# Cigarette-Smoke-Detection-and-Odor-Neutr.net
KiCad netlist of a schematic drawn in Altium Designer
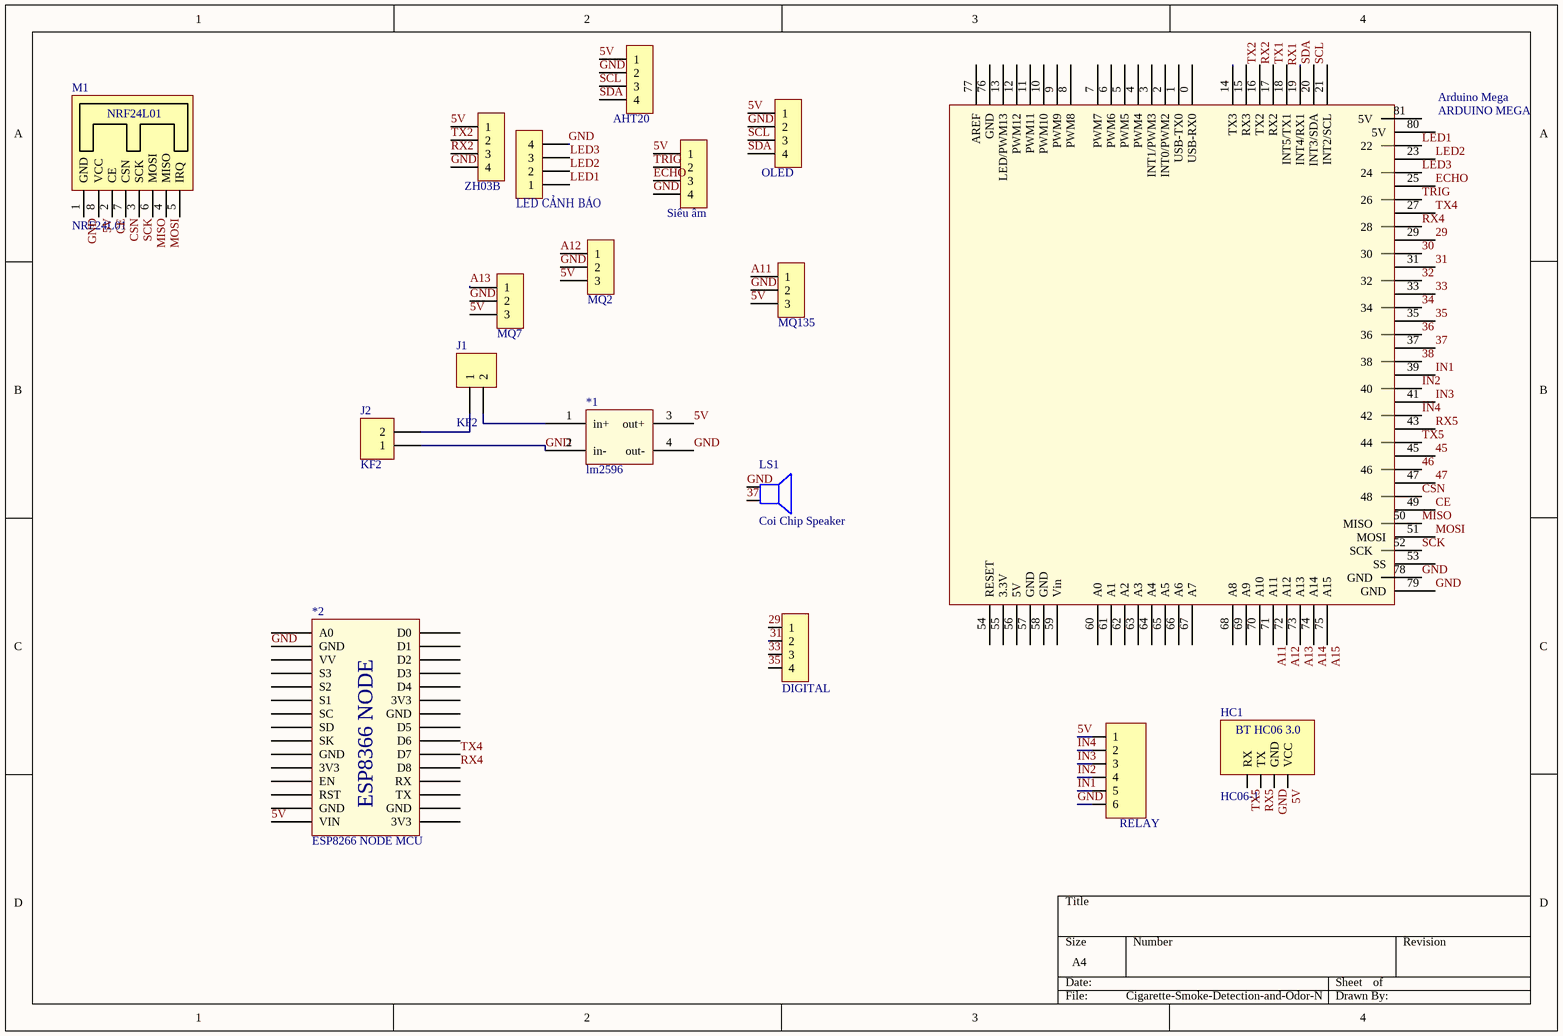
[diagram p0: Cigarette-Smoke-Detection-and-Odor-Neutralization-Robot.SchDoc]

(export (version "E")
  (design (tool "Eeschema 10.0.6"))
  (components
    (comp (ref "*1")
      (value "lm2596")
      (footprint "LM2596:PCBComponent_1")
      (libsource (lib "LM2596") (part "lm2596"))
    )
    (comp (ref "*2")
      (value "ESP8266 NODE MCU")
      (footprint "ESP8266 NODE MCU")
      (libsource (lib "Module1") (part "ESP8266 NODE MCU"))
    )
    (comp (ref "Arduino Mega")
      (value "ARDUINO MEGA")
      (footprint "ARDUINO MEGA")
      (libsource (lib "Arduino") (part "ARDUINO MEGA"))
    )
    (comp (ref "H1")
      (value "AHT20")
      (footprint "XH2.54M-4")
      (description "Cắm")
      (libsource (lib "Header") (part "Header 4P 2.54 Duc Thang"))
    )
    (comp (ref "H2")
      (value "OLED")
      (footprint "XH2.54M-4")
      (description "Cắm")
      (libsource (lib "Header") (part "Header 4P 2.54 Duc Thang"))
    )
    (comp (ref "H3")
      (value "ZH03B")
      (footprint "XH2.54M-4")
      (description "Cắm")
      (libsource (lib "Header") (part "Header 4P 2.54 Duc Thang"))
    )
    (comp (ref "H4")
      (value "LED CẢNH BÁO")
      (footprint "XH2.54M-4")
      (description "Cắm")
      (libsource (lib "") (part "Header 4P 2.54 Duc Thang_1"))
    )
    (comp (ref "H5")
      (value "Siêu âm")
      (footprint "XH2.54M-4")
      (description "Cắm")
      (libsource (lib "Header") (part "Header 4P 2.54 Duc Thang"))
    )
    (comp (ref "H6")
      (value "MQ2")
      (footprint "XH2.54M-3")
      (description "Cắm")
      (libsource (lib "Header") (part "Header 3P 2.54 Duc Thang"))
    )
    (comp (ref "H7")
      (value "MQ135")
      (footprint "XH2.54M-3")
      (description "Cắm")
      (libsource (lib "Header") (part "Header 3P 2.54 Duc Thang"))
    )
    (comp (ref "H8")
      (value "MQ7")
      (footprint "XH2.54M-3")
      (description "Cắm")
      (libsource (lib "Header") (part "Header 3P 2.54 Duc Thang"))
    )
    (comp (ref "H9")
      (value "RELAY")
      (footprint "JP 1x6 DT")
      (description "Cắm")
      (libsource (lib "Jump") (part "JP 1x6 2.54 Duc Thang"))
    )
    (comp (ref "HC1")
      (value "HC06-1")
      (footprint "HC06-1")
      (fields
        (field (name "MANUFACTURER") "Würth Elektronik eiSos GmbH")
        (field (name "PARTNO") "613004143121")
        (field (name "CREATED BY") "Karrer Zheng")
      )
      (libsource (lib "LIBRARY1") (part "HC06-1"))
    )
    (comp (ref "J1")
      (value "KF2")
      (footprint "KF2-3.5")
      (fields
        (field (name "MANUFACTURER") "Würth Elektronik eiSos GmbH")
        (field (name "PARTNO") "691103110002")
        (field (name "CREATED BY") "Karrer Zheng")
      )
      (libsource (lib "LIBRARY1") (part "KF2"))
    )
    (comp (ref "J2")
      (value "KF2")
      (footprint "KF2-3.5")
      (fields
        (field (name "MANUFACTURER") "Würth Elektronik eiSos GmbH")
        (field (name "PARTNO") "691103110002")
        (field (name "CREATED BY") "Karrer Zheng")
      )
      (libsource (lib "") (part "KF2_1"))
    )
    (comp (ref "JP1")
      (value "DIGITAL")
      (footprint "JP 1x4 DT")
      (description "Cắm")
      (libsource (lib "Jump") (part "JP 1x4 2.54 Duc Thang"))
    )
    (comp (ref "LS1")
      (value "Coi Chip Speaker")
      (footprint "Coi Chip Speacker")
      (description "Còi chip")
      (libsource (lib "Altium_Lib_by_KhueNguyenCreator") (part "Coi Chip Speaker"))
    )
    (comp (ref "M1") (value "NRF24L01") (footprint "NRF24L01") (libsource (lib "LIBRARY1") (part "NRF24L01")))
  )
  (nets
    (net (code "1") (name "/5V") (class "Default")
      (node (ref "*1") (pin "3") (pinfunction "out+_3") (pintype "passive"))
      (node (ref "*2") (pin "15") (pinfunction "VIN_15") (pintype "passive"))
      (node (ref "H1") (pin "1") (pinfunction "1_1") (pintype "passive"))
      (node (ref "H2") (pin "1") (pinfunction "1_1") (pintype "passive"))
      (node (ref "H3") (pin "1") (pinfunction "1_1") (pintype "passive"))
      (node (ref "H5") (pin "1") (pinfunction "1_1") (pintype "passive"))
      (node (ref "H6") (pin "3") (pinfunction "3_3") (pintype "passive"))
      (node (ref "H7") (pin "3") (pinfunction "3_3") (pintype "passive"))
      (node (ref "H8") (pin "3") (pinfunction "3_3") (pintype "passive"))
      (node (ref "H9") (pin "1") (pinfunction "1_1") (pintype "passive"))
      (node (ref "HC1") (pin "4") (pinfunction "VCC_4") (pintype "passive"))
      (node (ref "M1") (pin "8") (pinfunction "VCC_8") (pintype "passive"))
    )
    (net (code "2") (name "/29") (class "Default")
      (node (ref "Arduino Mega") (pin "29") (pinfunction "29_29") (pintype "passive"))
      (node (ref "JP1") (pin "1") (pinfunction "1_1") (pintype "passive"))
    )
    (net (code "3") (name "/30") (class "Default")
      (node (ref "Arduino Mega") (pin "30") (pinfunction "30_30") (pintype "passive"))
    )
    (net (code "4") (name "/31") (class "Default")
      (node (ref "Arduino Mega") (pin "31") (pinfunction "31_31") (pintype "passive"))
      (node (ref "JP1") (pin "2") (pinfunction "2_2") (pintype "passive"))
    )
    (net (code "5") (name "/32") (class "Default")
      (node (ref "Arduino Mega") (pin "32") (pinfunction "32_32") (pintype "passive"))
    )
    (net (code "6") (name "/33") (class "Default")
      (node (ref "Arduino Mega") (pin "33") (pinfunction "33_33") (pintype "passive"))
      (node (ref "JP1") (pin "3") (pinfunction "3_3") (pintype "passive"))
    )
    (net (code "7") (name "/34") (class "Default")
      (node (ref "Arduino Mega") (pin "34") (pinfunction "34_34") (pintype "passive"))
    )
    (net (code "8") (name "/35") (class "Default")
      (node (ref "Arduino Mega") (pin "35") (pinfunction "35_35") (pintype "passive"))
      (node (ref "JP1") (pin "4") (pinfunction "4_4") (pintype "passive"))
    )
    (net (code "9") (name "/36") (class "Default")
      (node (ref "Arduino Mega") (pin "36") (pinfunction "36_36") (pintype "passive"))
    )
    (net (code "10") (name "/37") (class "Default")
      (node (ref "Arduino Mega") (pin "37") (pinfunction "37_37") (pintype "passive"))
      (node (ref "LS1") (pin "2") (pinfunction "2_2") (pintype "passive"))
    )
    (net (code "11") (name "/38") (class "Default")
      (node (ref "Arduino Mega") (pin "38") (pinfunction "38_38") (pintype "passive"))
    )
    (net (code "12") (name "/45") (class "Default")
      (node (ref "Arduino Mega") (pin "45") (pinfunction "45_45") (pintype "passive"))
    )
    (net (code "13") (name "/46") (class "Default")
      (node (ref "Arduino Mega") (pin "46") (pinfunction "46_46") (pintype "passive"))
    )
    (net (code "14") (name "/47") (class "Default")
      (node (ref "Arduino Mega") (pin "47") (pinfunction "47_47") (pintype "passive"))
    )
    (net (code "15") (name "/A11") (class "Default")
      (node (ref "Arduino Mega") (pin "71") (pinfunction "A11_71") (pintype "passive"))
      (node (ref "H7") (pin "1") (pinfunction "1_1") (pintype "passive"))
    )
    (net (code "16") (name "/A12") (class "Default")
      (node (ref "Arduino Mega") (pin "72") (pinfunction "A12_72") (pintype "passive"))
      (node (ref "H6") (pin "1") (pinfunction "1_1") (pintype "passive"))
    )
    (net (code "17") (name "/A13") (class "Default")
      (node (ref "Arduino Mega") (pin "73") (pinfunction "A13_73") (pintype "passive"))
      (node (ref "H8") (pin "1") (pinfunction "1_1") (pintype "passive"))
    )
    (net (code "18") (name "/A14") (class "Default")
      (node (ref "Arduino Mega") (pin "74") (pinfunction "A14_74") (pintype "passive"))
    )
    (net (code "19") (name "/A15") (class "Default")
      (node (ref "Arduino Mega") (pin "75") (pinfunction "A15_75") (pintype "passive"))
    )
    (net (code "20") (name "/CE") (class "Default")
      (node (ref "Arduino Mega") (pin "49") (pinfunction "49_49") (pintype "passive"))
      (node (ref "M1") (pin "2") (pinfunction "CE_2") (pintype "passive"))
    )
    (net (code "21") (name "/CSN") (class "Default")
      (node (ref "Arduino Mega") (pin "48") (pinfunction "48_48") (pintype "passive"))
      (node (ref "M1") (pin "7") (pinfunction "CSN_7") (pintype "passive"))
    )
    (net (code "22") (name "/ECHO") (class "Default")
      (node (ref "Arduino Mega") (pin "25") (pinfunction "25_25") (pintype "passive"))
      (node (ref "H5") (pin "3") (pinfunction "3_3") (pintype "passive"))
    )
    (net (code "23") (name "/GND") (class "Default")
      (node (ref "*1") (pin "2") (pinfunction "in-_2") (pintype "passive"))
      (node (ref "*1") (pin "4") (pinfunction "out-_4") (pintype "passive"))
      (node (ref "*2") (pin "2") (pinfunction "GND_2") (pintype "passive"))
      (node (ref "Arduino Mega") (pin "78") (pinfunction "GND_78") (pintype "passive"))
      (node (ref "Arduino Mega") (pin "79") (pinfunction "GND_79") (pintype "passive"))
      (node (ref "H1") (pin "2") (pinfunction "2_2") (pintype "passive"))
      (node (ref "H2") (pin "2") (pinfunction "2_2") (pintype "passive"))
      (node (ref "H3") (pin "4") (pinfunction "4_4") (pintype "passive"))
      (node (ref "H4") (pin "4") (pinfunction "4_4") (pintype "passive"))
      (node (ref "H5") (pin "4") (pinfunction "4_4") (pintype "passive"))
      (node (ref "H6") (pin "2") (pinfunction "2_2") (pintype "passive"))
      (node (ref "H7") (pin "2") (pinfunction "2_2") (pintype "passive"))
      (node (ref "H8") (pin "2") (pinfunction "2_2") (pintype "passive"))
      (node (ref "H9") (pin "6") (pinfunction "6_6") (pintype "passive"))
      (node (ref "HC1") (pin "3") (pinfunction "GND_3") (pintype "passive"))
      (node (ref "J2") (pin "1") (pinfunction "1_1") (pintype "passive"))
      (node (ref "LS1") (pin "1") (pinfunction "1_1") (pintype "passive"))
      (node (ref "M1") (pin "1") (pinfunction "GND_1") (pintype "passive"))
    )
    (net (code "24") (name "/IN1") (class "Default")
      (node (ref "Arduino Mega") (pin "39") (pinfunction "39_39") (pintype "passive"))
      (node (ref "H9") (pin "5") (pinfunction "5_5") (pintype "passive"))
    )
    (net (code "25") (name "/IN2") (class "Default")
      (node (ref "Arduino Mega") (pin "40") (pinfunction "40_40") (pintype "passive"))
      (node (ref "H9") (pin "4") (pinfunction "4_4") (pintype "passive"))
    )
    (net (code "26") (name "/IN3") (class "Default")
      (node (ref "Arduino Mega") (pin "41") (pinfunction "41_41") (pintype "passive"))
      (node (ref "H9") (pin "3") (pinfunction "3_3") (pintype "passive"))
    )
    (net (code "27") (name "/IN4") (class "Default")
      (node (ref "Arduino Mega") (pin "42") (pinfunction "42_42") (pintype "passive"))
      (node (ref "H9") (pin "2") (pinfunction "2_2") (pintype "passive"))
    )
    (net (code "28") (name "/LED1") (class "Default")
      (node (ref "Arduino Mega") (pin "22") (pinfunction "22_22") (pintype "passive"))
      (node (ref "H4") (pin "1") (pinfunction "1_1") (pintype "passive"))
    )
    (net (code "29") (name "/LED2") (class "Default")
      (node (ref "Arduino Mega") (pin "23") (pinfunction "23_23") (pintype "passive"))
      (node (ref "H4") (pin "2") (pinfunction "2_2") (pintype "passive"))
    )
    (net (code "30") (name "/LED3") (class "Default")
      (node (ref "Arduino Mega") (pin "24") (pinfunction "24_24") (pintype "passive"))
      (node (ref "H4") (pin "3") (pinfunction "3_3") (pintype "passive"))
    )
    (net (code "31") (name "/MISO") (class "Default")
      (node (ref "Arduino Mega") (pin "50") (pinfunction "MISO_50") (pintype "passive"))
      (node (ref "M1") (pin "6") (pinfunction "MOSI_6") (pintype "passive"))
    )
    (net (code "32") (name "/MOSI") (class "Default")
      (node (ref "Arduino Mega") (pin "51") (pinfunction "MOSI_51") (pintype "passive"))
      (node (ref "M1") (pin "4") (pinfunction "MISO_4") (pintype "passive"))
    )
    (net (code "33") (name "/RX1") (class "Default")
      (node (ref "Arduino Mega") (pin "19") (pinfunction "INT4/RX1_19") (pintype "passive"))
    )
    (net (code "34") (name "/RX2") (class "Default")
      (node (ref "Arduino Mega") (pin "17") (pinfunction "RX2_17") (pintype "passive"))
      (node (ref "H3") (pin "3") (pinfunction "3_3") (pintype "passive"))
    )
    (net (code "35") (name "/RX4") (class "Default")
      (node (ref "*2") (pin "20") (pinfunction "D8_20") (pintype "passive"))
      (node (ref "Arduino Mega") (pin "28") (pinfunction "28_28") (pintype "passive"))
    )
    (net (code "36") (name "/RX5") (class "Default")
      (node (ref "Arduino Mega") (pin "43") (pinfunction "43_43") (pintype "passive"))
      (node (ref "HC1") (pin "2") (pinfunction "TX_2") (pintype "passive"))
    )
    (net (code "37") (name "/SCK") (class "Default")
      (node (ref "Arduino Mega") (pin "52") (pinfunction "SCK_52") (pintype "passive"))
      (node (ref "M1") (pin "3") (pinfunction "SCK_3") (pintype "passive"))
    )
    (net (code "38") (name "/SCL") (class "Default")
      (node (ref "Arduino Mega") (pin "21") (pinfunction "INT2/SCL_21") (pintype "passive"))
      (node (ref "H1") (pin "3") (pinfunction "3_3") (pintype "passive"))
      (node (ref "H2") (pin "3") (pinfunction "3_3") (pintype "passive"))
    )
    (net (code "39") (name "/SDA") (class "Default")
      (node (ref "Arduino Mega") (pin "20") (pinfunction "INT3/SDA_20") (pintype "passive"))
      (node (ref "H1") (pin "4") (pinfunction "4_4") (pintype "passive"))
      (node (ref "H2") (pin "4") (pinfunction "4_4") (pintype "passive"))
    )
    (net (code "40") (name "/TRIG") (class "Default")
      (node (ref "Arduino Mega") (pin "26") (pinfunction "26_26") (pintype "passive"))
      (node (ref "H5") (pin "2") (pinfunction "2_2") (pintype "passive"))
    )
    (net (code "41") (name "/TX1") (class "Default")
      (node (ref "Arduino Mega") (pin "18") (pinfunction "INT5/TX1_18") (pintype "passive"))
    )
    (net (code "42") (name "/TX2") (class "Default")
      (node (ref "Arduino Mega") (pin "16") (pinfunction "TX2_16") (pintype "passive"))
      (node (ref "H3") (pin "2") (pinfunction "2_2") (pintype "passive"))
    )
    (net (code "43") (name "/TX4") (class "Default")
      (node (ref "*2") (pin "21") (pinfunction "D7_21") (pintype "passive"))
      (node (ref "Arduino Mega") (pin "27") (pinfunction "27_27") (pintype "passive"))
    )
    (net (code "44") (name "/TX5") (class "Default")
      (node (ref "Arduino Mega") (pin "44") (pinfunction "44_44") (pintype "passive"))
      (node (ref "HC1") (pin "1") (pinfunction "RX_1") (pintype "passive"))
    )
    (net (code "45") (name "Net-(*1-in+)") (class "Default")
      (node (ref "*1") (pin "1") (pinfunction "in+_1") (pintype "passive"))
      (node (ref "J1") (pin "2") (pinfunction "2_2") (pintype "passive"))
    )
    (net (code "46") (name "Net-(J1-Pad1)") (class "Default")
      (node (ref "J1") (pin "1") (pinfunction "1_1") (pintype "passive"))
      (node (ref "J2") (pin "2") (pinfunction "2_2") (pintype "passive"))
    )
    (net (code "47") (name "unconnected-(*2-3V3-Pad11)") (class "Default")
      (node (ref "*2") (pin "11") (pinfunction "3V3_11") (pintype "passive"))
    )
    (net (code "48") (name "unconnected-(*2-3V3-Pad16)") (class "Default")
      (node (ref "*2") (pin "16") (pinfunction "3V3_16") (pintype "passive"))
    )
    (net (code "49") (name "unconnected-(*2-3V3-Pad25)") (class "Default")
      (node (ref "*2") (pin "25") (pinfunction "3V3_25") (pintype "passive"))
    )
    (net (code "50") (name "unconnected-(*2-A0-Pad1)") (class "Default")
      (node (ref "*2") (pin "1") (pinfunction "A0_1") (pintype "passive"))
    )
    (net (code "51") (name "unconnected-(*2-D0-Pad30)") (class "Default")
      (node (ref "*2") (pin "30") (pinfunction "D0_30") (pintype "passive"))
    )
    (net (code "52") (name "unconnected-(*2-D1-Pad29)") (class "Default")
      (node (ref "*2") (pin "29") (pinfunction "D1_29") (pintype "passive"))
    )
    (net (code "53") (name "unconnected-(*2-D2-Pad28)") (class "Default")
      (node (ref "*2") (pin "28") (pinfunction "D2_28") (pintype "passive"))
    )
    (net (code "54") (name "unconnected-(*2-D3-Pad27)") (class "Default")
      (node (ref "*2") (pin "27") (pinfunction "D3_27") (pintype "passive"))
    )
    (net (code "55") (name "unconnected-(*2-D4-Pad26)") (class "Default")
      (node (ref "*2") (pin "26") (pinfunction "D4_26") (pintype "passive"))
    )
    (net (code "56") (name "unconnected-(*2-D5-Pad23)") (class "Default")
      (node (ref "*2") (pin "23") (pinfunction "D5_23") (pintype "passive"))
    )
    (net (code "57") (name "unconnected-(*2-D6-Pad22)") (class "Default")
      (node (ref "*2") (pin "22") (pinfunction "D6_22") (pintype "passive"))
    )
    (net (code "58") (name "unconnected-(*2-EN-Pad12)") (class "Default")
      (node (ref "*2") (pin "12") (pinfunction "EN_12") (pintype "passive"))
    )
    (net (code "59") (name "unconnected-(*2-GND-Pad10)") (class "Default")
      (node (ref "*2") (pin "10") (pinfunction "GND_10") (pintype "passive"))
    )
    (net (code "60") (name "unconnected-(*2-GND-Pad14)") (class "Default")
      (node (ref "*2") (pin "14") (pinfunction "GND_14") (pintype "passive"))
    )
    (net (code "61") (name "unconnected-(*2-GND-Pad17)") (class "Default")
      (node (ref "*2") (pin "17") (pinfunction "GND_17") (pintype "passive"))
    )
    (net (code "62") (name "unconnected-(*2-GND-Pad24)") (class "Default")
      (node (ref "*2") (pin "24") (pinfunction "GND_24") (pintype "passive"))
    )
    (net (code "63") (name "unconnected-(*2-RST-Pad13)") (class "Default")
      (node (ref "*2") (pin "13") (pinfunction "RST_13") (pintype "passive"))
    )
    (net (code "64") (name "unconnected-(*2-RX-Pad19)") (class "Default")
      (node (ref "*2") (pin "19") (pinfunction "RX_19") (pintype "passive"))
    )
    (net (code "65") (name "unconnected-(*2-S1-Pad6)") (class "Default")
      (node (ref "*2") (pin "6") (pinfunction "S1_6") (pintype "passive"))
    )
    (net (code "66") (name "unconnected-(*2-S2-Pad5)") (class "Default")
      (node (ref "*2") (pin "5") (pinfunction "S2_5") (pintype "passive"))
    )
    (net (code "67") (name "unconnected-(*2-S3-Pad4)") (class "Default")
      (node (ref "*2") (pin "4") (pinfunction "S3_4") (pintype "passive"))
    )
    (net (code "68") (name "unconnected-(*2-SC-Pad7)") (class "Default")
      (node (ref "*2") (pin "7") (pinfunction "SC_7") (pintype "passive"))
    )
    (net (code "69") (name "unconnected-(*2-SD-Pad8)") (class "Default")
      (node (ref "*2") (pin "8") (pinfunction "SD_8") (pintype "passive"))
    )
    (net (code "70") (name "unconnected-(*2-SK-Pad9)") (class "Default")
      (node (ref "*2") (pin "9") (pinfunction "SK_9") (pintype "passive"))
    )
    (net (code "71") (name "unconnected-(*2-TX-Pad18)") (class "Default")
      (node (ref "*2") (pin "18") (pinfunction "TX_18") (pintype "passive"))
    )
    (net (code "72") (name "unconnected-(*2-VV-Pad3)") (class "Default")
      (node (ref "*2") (pin "3") (pinfunction "VV_3") (pintype "passive"))
    )
    (net (code "73") (name "unconnected-(Arduino Mega-3.3V-Pad55)") (class "Default")
      (node (ref "Arduino Mega") (pin "55") (pinfunction "3.3V_55") (pintype "passive"))
    )
    (net (code "74") (name "unconnected-(Arduino Mega-5V-Pad56)") (class "Default")
      (node (ref "Arduino Mega") (pin "56") (pinfunction "5V_56") (pintype "passive"))
    )
    (net (code "75") (name "unconnected-(Arduino Mega-5V-Pad80)") (class "Default")
      (node (ref "Arduino Mega") (pin "80") (pinfunction "5V_80") (pintype "passive"))
    )
    (net (code "76") (name "unconnected-(Arduino Mega-5V-Pad81)") (class "Default")
      (node (ref "Arduino Mega") (pin "81") (pinfunction "5V_81") (pintype "passive"))
    )
    (net (code "77") (name "unconnected-(Arduino Mega-A0-Pad60)") (class "Default")
      (node (ref "Arduino Mega") (pin "60") (pinfunction "A0_60") (pintype "passive"))
    )
    (net (code "78") (name "unconnected-(Arduino Mega-A1-Pad61)") (class "Default")
      (node (ref "Arduino Mega") (pin "61") (pinfunction "A1_61") (pintype "passive"))
    )
    (net (code "79") (name "unconnected-(Arduino Mega-A2-Pad62)") (class "Default")
      (node (ref "Arduino Mega") (pin "62") (pinfunction "A2_62") (pintype "passive"))
    )
    (net (code "80") (name "unconnected-(Arduino Mega-A3-Pad63)") (class "Default")
      (node (ref "Arduino Mega") (pin "63") (pinfunction "A3_63") (pintype "passive"))
    )
    (net (code "81") (name "unconnected-(Arduino Mega-A4-Pad64)") (class "Default")
      (node (ref "Arduino Mega") (pin "64") (pinfunction "A4_64") (pintype "passive"))
    )
    (net (code "82") (name "unconnected-(Arduino Mega-A5-Pad65)") (class "Default")
      (node (ref "Arduino Mega") (pin "65") (pinfunction "A5_65") (pintype "passive"))
    )
    (net (code "83") (name "unconnected-(Arduino Mega-A6-Pad66)") (class "Default")
      (node (ref "Arduino Mega") (pin "66") (pinfunction "A6_66") (pintype "passive"))
    )
    (net (code "84") (name "unconnected-(Arduino Mega-A7-Pad67)") (class "Default")
      (node (ref "Arduino Mega") (pin "67") (pinfunction "A7_67") (pintype "passive"))
    )
    (net (code "85") (name "unconnected-(Arduino Mega-A8-Pad68)") (class "Default")
      (node (ref "Arduino Mega") (pin "68") (pinfunction "A8_68") (pintype "passive"))
    )
    (net (code "86") (name "unconnected-(Arduino Mega-A9-Pad69)") (class "Default")
      (node (ref "Arduino Mega") (pin "69") (pinfunction "A9_69") (pintype "passive"))
    )
    (net (code "87") (name "unconnected-(Arduino Mega-A10-Pad70)") (class "Default")
      (node (ref "Arduino Mega") (pin "70") (pinfunction "A10_70") (pintype "passive"))
    )
    (net (code "88") (name "unconnected-(Arduino Mega-AREF-Pad77)") (class "Default")
      (node (ref "Arduino Mega") (pin "77") (pinfunction "AREF_77") (pintype "passive"))
    )
    (net (code "89") (name "unconnected-(Arduino Mega-GND-Pad57)") (class "Default")
      (node (ref "Arduino Mega") (pin "57") (pinfunction "GND_57") (pintype "passive"))
    )
    (net (code "90") (name "unconnected-(Arduino Mega-GND-Pad58)") (class "Default")
      (node (ref "Arduino Mega") (pin "58") (pinfunction "GND_58") (pintype "passive"))
    )
    (net (code "91") (name "unconnected-(Arduino Mega-GND-Pad76)") (class "Default")
      (node (ref "Arduino Mega") (pin "76") (pinfunction "GND_76") (pintype "passive"))
    )
    (net (code "92") (name "unconnected-(Arduino Mega-INT0{slash}PWM2-Pad2)") (class "Default")
      (node (ref "Arduino Mega") (pin "2") (pinfunction "INT0/PWM2_2") (pintype "passive"))
    )
    (net (code "93") (name "unconnected-(Arduino Mega-INT1{slash}PWM3-Pad3)") (class "Default")
      (node (ref "Arduino Mega") (pin "3") (pinfunction "INT1/PWM3_3") (pintype "passive"))
    )
    (net (code "94") (name "unconnected-(Arduino Mega-LED{slash}PWM13-Pad13)") (class "Default")
      (node (ref "Arduino Mega") (pin "13") (pinfunction "LED/PWM13_13") (pintype "passive"))
    )
    (net (code "95") (name "unconnected-(Arduino Mega-PWM4-Pad4)") (class "Default")
      (node (ref "Arduino Mega") (pin "4") (pinfunction "PWM4_4") (pintype "passive"))
    )
    (net (code "96") (name "unconnected-(Arduino Mega-PWM5-Pad5)") (class "Default")
      (node (ref "Arduino Mega") (pin "5") (pinfunction "PWM5_5") (pintype "passive"))
    )
    (net (code "97") (name "unconnected-(Arduino Mega-PWM6-Pad6)") (class "Default")
      (node (ref "Arduino Mega") (pin "6") (pinfunction "PWM6_6") (pintype "passive"))
    )
    (net (code "98") (name "unconnected-(Arduino Mega-PWM7-Pad7)") (class "Default")
      (node (ref "Arduino Mega") (pin "7") (pinfunction "PWM7_7") (pintype "passive"))
    )
    (net (code "99") (name "unconnected-(Arduino Mega-PWM8-Pad8)") (class "Default")
      (node (ref "Arduino Mega") (pin "8") (pinfunction "PWM8_8") (pintype "passive"))
    )
    (net (code "100") (name "unconnected-(Arduino Mega-PWM9-Pad9)") (class "Default")
      (node (ref "Arduino Mega") (pin "9") (pinfunction "PWM9_9") (pintype "passive"))
    )
    (net (code "101") (name "unconnected-(Arduino Mega-PWM10-Pad10)") (class "Default")
      (node (ref "Arduino Mega") (pin "10") (pinfunction "PWM10_10") (pintype "passive"))
    )
    (net (code "102") (name "unconnected-(Arduino Mega-PWM11-Pad11)") (class "Default")
      (node (ref "Arduino Mega") (pin "11") (pinfunction "PWM11_11") (pintype "passive"))
    )
    (net (code "103") (name "unconnected-(Arduino Mega-PWM12-Pad12)") (class "Default")
      (node (ref "Arduino Mega") (pin "12") (pinfunction "PWM12_12") (pintype "passive"))
    )
    (net (code "104") (name "unconnected-(Arduino Mega-RESET-Pad54)") (class "Default")
      (node (ref "Arduino Mega") (pin "54") (pinfunction "RESET_54") (pintype "passive"))
    )
    (net (code "105") (name "unconnected-(Arduino Mega-RX3-Pad15)") (class "Default")
      (node (ref "Arduino Mega") (pin "15") (pinfunction "RX3_15") (pintype "passive"))
    )
    (net (code "106") (name "unconnected-(Arduino Mega-SS-Pad53)") (class "Default")
      (node (ref "Arduino Mega") (pin "53") (pinfunction "SS_53") (pintype "passive"))
    )
    (net (code "107") (name "unconnected-(Arduino Mega-TX3-Pad14)") (class "Default")
      (node (ref "Arduino Mega") (pin "14") (pinfunction "TX3_14") (pintype "passive"))
    )
    (net (code "108") (name "unconnected-(Arduino Mega-USB-RX0-Pad0)") (class "Default")
      (node (ref "Arduino Mega") (pin "0") (pinfunction "USB-RX0_0") (pintype "passive"))
    )
    (net (code "109") (name "unconnected-(Arduino Mega-USB-TX0-Pad1)") (class "Default")
      (node (ref "Arduino Mega") (pin "1") (pinfunction "USB-TX0_1") (pintype "passive"))
    )
    (net (code "110") (name "unconnected-(Arduino Mega-Vin-Pad59)") (class "Default")
      (node (ref "Arduino Mega") (pin "59") (pinfunction "Vin_59") (pintype "passive"))
    )
    (net (code "111") (name "unconnected-(M1-IRQ-Pad5)") (class "Default")
      (node (ref "M1") (pin "5") (pinfunction "IRQ_5") (pintype "passive"))
    )
  )
)
